# MAIN.net
KiCad netlist of a schematic drawn in Altium Designer
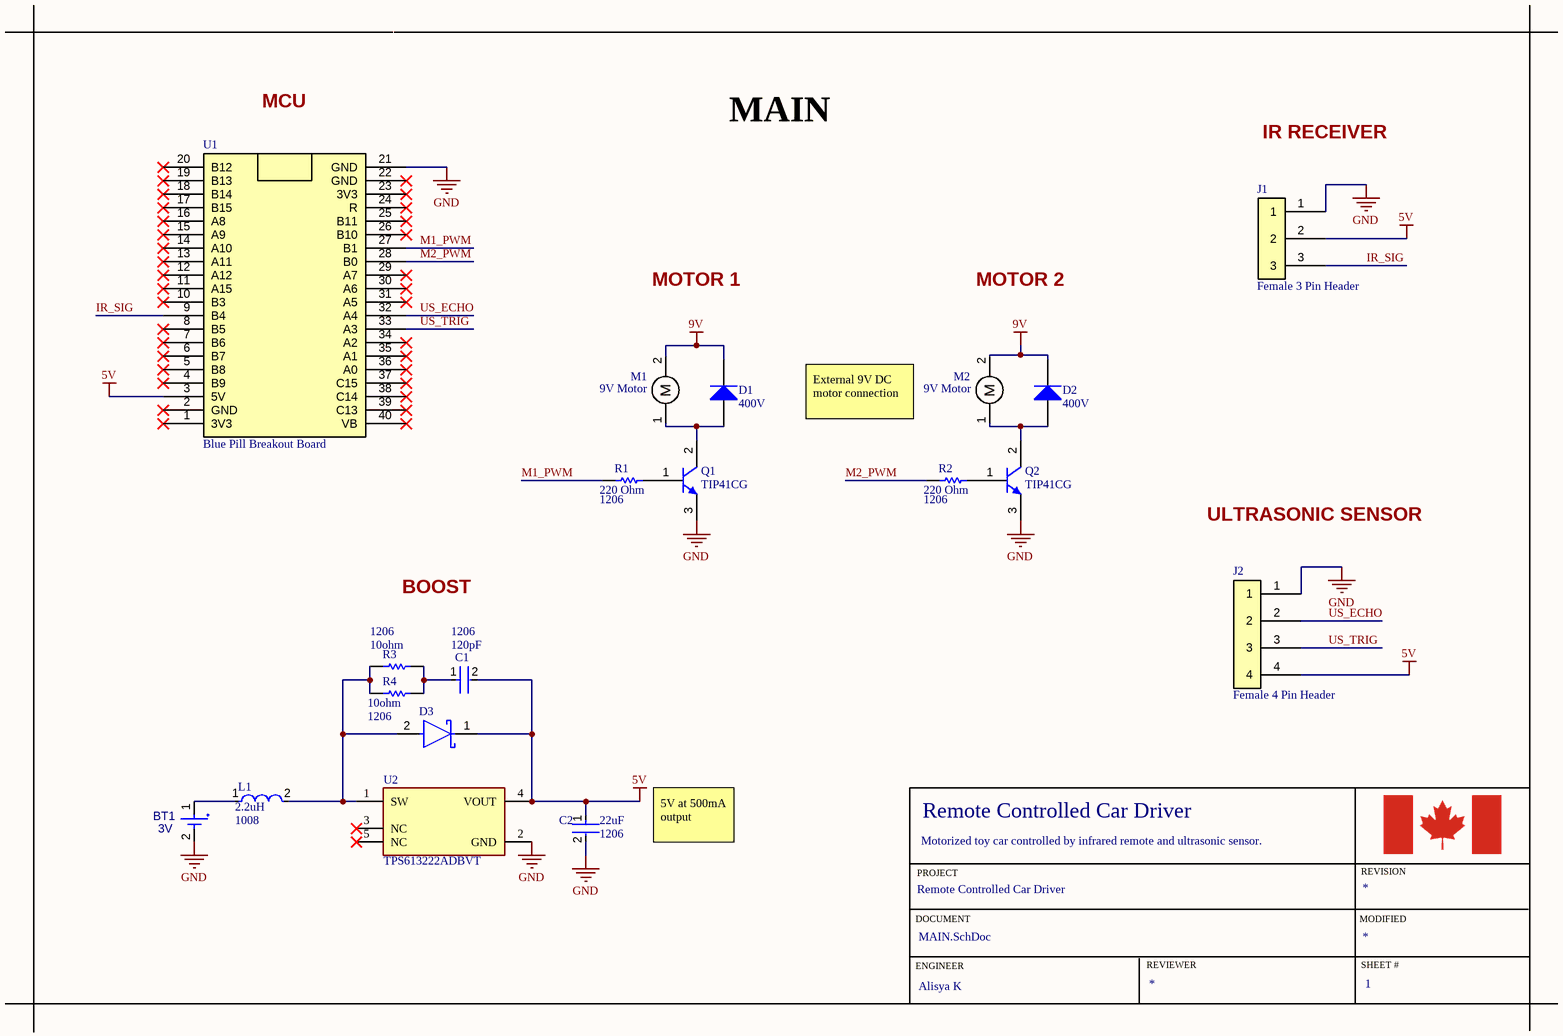
[diagram p0: MAIN.SchDoc]

(export (version "E")
  (design (tool "Eeschema 10.0.6"))
  (components
    (comp (ref "BT1")
      (value "3V")
      (footprint "New footprint 1")
      (libsource (lib "pcb stuff") (part "CMP-00622-2"))
    )
    (comp (ref "C1")
      (value "GRM31A7U3A121JW31D")
      (footprint "FP-GRM31A-0_2-e0_3_0_95-IPC_B")
      (description "Chip Multilayer Ceramic Capacitors for General Purpose, 1206, 120pF, U2J, -750ppm/°C, 5%, 1kV")
      (fields
        (field (name "CASE/PACKAGE") "1206")
        (field (name "TOLERANCE") "5%")
        (field (name "CAPACITANCE") "120pF")
      )
      (libsource (lib "Altium Content Vault") (part "b4654b650e69147ec39a6b967a45e02"))
    )
    (comp (ref "C2")
      (value "C3216X5R1V226M160AC")
      (footprint "FP-C3216-160-0_2-IPC_B")
      (description "Multilayer Ceramic Capacitors 22uF ±20% 35V X5R SMD 1206")
      (fields
        (field (name "CASE/PACKAGE") "1206")
        (field (name "TOLERANCE") "20%")
        (field (name "VOLTAGE") "35V")
        (field (name "CAPACITANCE") "22uF")
      )
      (libsource (lib "Altium Content Vault") (part "11868f565c42a9108669ba33697ecf6"))
    )
    (comp (ref "D1")
      (value "S1G-13-F")
      (footprint "DIOD-SMA-2_V")
      (description "Glass Passivated Rectifier, 1 A, 400 V, -65 to 150 degC, 2-Pin SMD, RoHS, Tape and Reel")
      (fields (field (name "REVERSE VOLTAGE-MAX [VRRM]") "400V") (field (name "MANUFACTURER") "Diodes Inc"))
      (libsource (lib "Altium Content Vault") (part "D-AK-2"))
    )
    (comp (ref "D2")
      (value "S1G-13-F")
      (footprint "DIOD-SMA-2_V")
      (description "Glass Passivated Rectifier, 1 A, 400 V, -65 to 150 degC, 2-Pin SMD, RoHS, Tape and Reel")
      (fields (field (name "REVERSE VOLTAGE-MAX [VRRM]") "400V") (field (name "MANUFACTURER") "Diodes Inc"))
      (libsource (lib "Altium Content Vault") (part "D-AK-2"))
    )
    (comp (ref "D3")
      (value "MSS1P4-M3/89A")
      (footprint "FP-96591-MFG")
      (description "DIODE SCHOTTKY 40V 1A MICROSMP")
      (fields
        (field (name "OCTOPART") "https://octopart.com/mss1p4-m3%2F89a-vishay-42505723")
        (field (name "MANUFACTURER") "Vishay")
      )
      (libsource (lib "Altium Content Vault") (part "c1678fac7984e62e0809fbf79c06691"))
    )
    (comp (ref "J1")
      (value "Female 3 Pin Header")
      (footprint "Female 4 Pin Header-Footprint-1")
      (libsource (lib "pcb stuff") (part "Female 3 Pin Header-Symbol-1"))
    )
    (comp (ref "J2")
      (value "Female 4 Pin Header")
      (footprint "Female 4 Pin Header-Footprint-1")
      (libsource (lib "pcb stuff") (part "Female 4 Pin Header-Symbol-1"))
    )
    (comp (ref "L1")
      (value "DFE252012F-2R2M=P2")
      (footprint "FP-DFE252012C-IPC_B")
      (description "Shielded Wirewound Inductor 2.2uH 20% 2300mA 0.082Ω 1008 (2520)")
      (fields
        (field (name "CASE/PACKAGE") "1008")
        (field (name "TOLERANCE") "20%")
        (field (name "INDUCTANCE") "2.2uH")
      )
      (libsource (lib "Altium Content Vault") (part "725321dda6339637d4d059423bc1c3c"))
    )
    (comp (ref "M1")
      (value "9V Motor")
      (footprint "9V Motor-Footprint-1")
      (libsource (lib "pcb stuff") (part "9V Motor-Symbol-1"))
    )
    (comp (ref "M2")
      (value "9V Motor")
      (footprint "9V Motor-Footprint-1")
      (libsource (lib "pcb stuff") (part "9V Motor-Symbol-1"))
    )
    (comp (ref "Q1")
      (value "TIP41CG")
      (footprint "ONSC-TO-220-3-221A-09")
      (description "Complementary Silicon Plastic Power Transistor, 3-Pin TO-220, Pb-Free, Tube")
      (fields (field (name "MANUFACTURER") "On Semiconductor"))
      (libsource (lib "Altium Content Vault") (part "ONSC-NPN-B1C2E3-3_C"))
    )
    (comp (ref "Q2")
      (value "TIP41CG")
      (footprint "ONSC-TO-220-3-221A-09")
      (description "Complementary Silicon Plastic Power Transistor, 3-Pin TO-220, Pb-Free, Tube")
      (fields (field (name "MANUFACTURER") "On Semiconductor"))
      (libsource (lib "Altium Content Vault") (part "ONSC-NPN-B1C2E3-3_C"))
    )
    (comp (ref "R1")
      (value "220 Ohm")
      (footprint "RESC3216X60X45ML10T20")
      (fields
        (field (name "MANUFACTURER") "Vishay Dale")
        (field (name "PART NUMBER") "CRCW1206220RFKEA")
        (field (name "PACKAGE") "1206")
      )
      (libsource (lib "Altium Content Vault") (part "RES"))
    )
    (comp (ref "R2")
      (value "220 Ohm")
      (footprint "RESC3216X60X45ML10T20")
      (fields
        (field (name "MANUFACTURER") "Vishay Dale")
        (field (name "PART NUMBER") "CRCW1206220RFKEA")
        (field (name "PACKAGE") "1206")
      )
      (libsource (lib "Altium Content Vault") (part "RES"))
    )
    (comp (ref "R3")
      (value "10ohm")
      (footprint "RESC3216X60X45NL10T20")
      (fields
        (field (name "PART NUMBER") "CRCW120610R0FKTA")
        (field (name "MANUFACTURER") "Vishay Dale")
        (field (name "PACKAGE") "1206")
      )
      (libsource (lib "Altium Content Vault") (part "RES"))
    )
    (comp (ref "R4")
      (value "10ohm")
      (footprint "RESC3216X60X45NL10T20")
      (fields
        (field (name "PART NUMBER") "CRCW120610R0FKTA")
        (field (name "MANUFACTURER") "Vishay Dale")
        (field (name "PACKAGE") "1206")
      )
      (libsource (lib "Altium Content Vault") (part "RES"))
    )
    (comp (ref "U1")
      (value "Blue Pill Breakout Board")
      (footprint "Blue Pill Breakout Board-Footprint-1")
      (description "STM32F103C6T6A")
      (libsource (lib "pcb stuff") (part "Blue Pill Breakout Board-Symbol-1"))
    )
    (comp (ref "U2")
      (value "TPS613222ADBVT")
      (footprint "FP-DBV0005A-MFG")
      (description "IC REG BOOST 5V 2.5A SOT23-5")
      (libsource (lib "Altium Content Vault") (part "046d2554ad9af14250d30b20e3f80a1"))
    )
  )
  (nets
    (net (code "1") (name "/IR_SIG") (class "Default")
      (node (ref "J1") (pin "3") (pinfunction "3_3") (pintype "passive"))
      (node (ref "U1") (pin "9") (pinfunction "B4_9") (pintype "passive"))
    )
    (net (code "2") (name "/M1_PWM") (class "Default")
      (node (ref "R1") (pin "1") (pinfunction "1_1") (pintype "passive"))
      (node (ref "U1") (pin "27") (pinfunction "B1_27") (pintype "passive"))
    )
    (net (code "3") (name "/M2_PWM") (class "Default")
      (node (ref "R2") (pin "1") (pinfunction "1_1") (pintype "passive"))
      (node (ref "U1") (pin "28") (pinfunction "B0_28") (pintype "passive"))
    )
    (net (code "4") (name "/US_ECHO") (class "Default")
      (node (ref "J2") (pin "2") (pinfunction "2_2") (pintype "passive"))
      (node (ref "U1") (pin "32") (pinfunction "A4_32") (pintype "passive"))
    )
    (net (code "5") (name "/US_TRIG") (class "Default")
      (node (ref "J2") (pin "3") (pinfunction "3_3") (pintype "passive"))
      (node (ref "U1") (pin "33") (pinfunction "A3_33") (pintype "passive"))
    )
    (net (code "6") (name "5V") (class "Default")
      (node (ref "C1") (pin "2") (pinfunction "2_2") (pintype "passive"))
      (node (ref "C2") (pin "1") (pinfunction "1_1") (pintype "passive"))
      (node (ref "D3") (pin "1") (pinfunction "C_1") (pintype "passive"))
      (node (ref "J1") (pin "2") (pinfunction "2_2") (pintype "passive"))
      (node (ref "J2") (pin "4") (pinfunction "4_4") (pintype "passive"))
      (node (ref "U1") (pin "3") (pinfunction "5V_3") (pintype "passive"))
      (node (ref "U2") (pin "4") (pinfunction "VOUT_4") (pintype "power_in"))
    )
    (net (code "7") (name "9V") (class "Default")
      (node (ref "D1") (pin "2") (pinfunction "K_2") (pintype "passive"))
      (node (ref "D2") (pin "2") (pinfunction "K_2") (pintype "passive"))
      (node (ref "M1") (pin "2") (pinfunction "19_2") (pintype "passive"))
      (node (ref "M2") (pin "2") (pinfunction "19_2") (pintype "passive"))
    )
    (net (code "8") (name "GND") (class "Default")
      (node (ref "BT1") (pin "2") (pinfunction "-_2") (pintype "passive"))
      (node (ref "C2") (pin "2") (pinfunction "2_2") (pintype "passive"))
      (node (ref "J1") (pin "1") (pinfunction "1_1") (pintype "passive"))
      (node (ref "J2") (pin "1") (pinfunction "1_1") (pintype "passive"))
      (node (ref "Q1") (pin "3") (pinfunction "E_3") (pintype "passive"))
      (node (ref "Q2") (pin "3") (pinfunction "E_3") (pintype "passive"))
      (node (ref "U1") (pin "21") (pinfunction "GND_21") (pintype "passive"))
      (node (ref "U2") (pin "2") (pinfunction "GND_2") (pintype "power_in"))
    )
    (net (code "9") (name "Net-(BT1-+)") (class "Default")
      (node (ref "BT1") (pin "1") (pinfunction "+_1") (pintype "passive"))
      (node (ref "L1") (pin "1") (pinfunction "1_1") (pintype "passive"))
    )
    (net (code "10") (name "Net-(C1-Pad1)") (class "Default")
      (node (ref "C1") (pin "1") (pinfunction "1_1") (pintype "passive"))
      (node (ref "R3") (pin "2") (pinfunction "2_2") (pintype "passive"))
      (node (ref "R4") (pin "2") (pinfunction "2_2") (pintype "passive"))
    )
    (net (code "11") (name "Net-(D1-A)") (class "Default")
      (node (ref "D1") (pin "1") (pinfunction "A_1") (pintype "passive"))
      (node (ref "M1") (pin "1") (pinfunction "18_1") (pintype "passive"))
      (node (ref "Q1") (pin "2") (pinfunction "C_2") (pintype "passive"))
    )
    (net (code "12") (name "Net-(D2-A)") (class "Default")
      (node (ref "D2") (pin "1") (pinfunction "A_1") (pintype "passive"))
      (node (ref "M2") (pin "1") (pinfunction "18_1") (pintype "passive"))
      (node (ref "Q2") (pin "2") (pinfunction "C_2") (pintype "passive"))
    )
    (net (code "13") (name "Net-(D3-A)") (class "Default")
      (node (ref "D3") (pin "2") (pinfunction "A_2") (pintype "passive"))
      (node (ref "L1") (pin "2") (pinfunction "2_2") (pintype "passive"))
      (node (ref "R3") (pin "1") (pinfunction "1_1") (pintype "passive"))
      (node (ref "R4") (pin "1") (pinfunction "1_1") (pintype "passive"))
      (node (ref "U2") (pin "1") (pinfunction "SW_1") (pintype "passive"))
    )
    (net (code "14") (name "Net-(Q1-B)") (class "Default")
      (node (ref "Q1") (pin "1") (pinfunction "B_1") (pintype "passive"))
      (node (ref "R1") (pin "2") (pinfunction "2_2") (pintype "passive"))
    )
    (net (code "15") (name "Net-(Q2-B)") (class "Default")
      (node (ref "Q2") (pin "1") (pinfunction "B_1") (pintype "passive"))
      (node (ref "R2") (pin "2") (pinfunction "2_2") (pintype "passive"))
    )
    (net (code "16") (name "unconnected-(U1-3V3-Pad1)") (class "Default")
      (node (ref "U1") (pin "1") (pinfunction "3V3_1") (pintype "passive+no_connect"))
    )
    (net (code "17") (name "unconnected-(U1-3V3-Pad23)") (class "Default")
      (node (ref "U1") (pin "23") (pinfunction "3V3_23") (pintype "passive+no_connect"))
    )
    (net (code "18") (name "unconnected-(U1-A0-Pad36)") (class "Default")
      (node (ref "U1") (pin "36") (pinfunction "A0_36") (pintype "passive+no_connect"))
    )
    (net (code "19") (name "unconnected-(U1-A1-Pad35)") (class "Default")
      (node (ref "U1") (pin "35") (pinfunction "A1_35") (pintype "passive+no_connect"))
    )
    (net (code "20") (name "unconnected-(U1-A2-Pad34)") (class "Default")
      (node (ref "U1") (pin "34") (pinfunction "A2_34") (pintype "passive+no_connect"))
    )
    (net (code "21") (name "unconnected-(U1-A5-Pad31)") (class "Default")
      (node (ref "U1") (pin "31") (pinfunction "A5_31") (pintype "passive+no_connect"))
    )
    (net (code "22") (name "unconnected-(U1-A6-Pad30)") (class "Default")
      (node (ref "U1") (pin "30") (pinfunction "A6_30") (pintype "passive+no_connect"))
    )
    (net (code "23") (name "unconnected-(U1-A7-Pad29)") (class "Default")
      (node (ref "U1") (pin "29") (pinfunction "A7_29") (pintype "passive+no_connect"))
    )
    (net (code "24") (name "unconnected-(U1-A8-Pad16)") (class "Default")
      (node (ref "U1") (pin "16") (pinfunction "A8_16") (pintype "passive+no_connect"))
    )
    (net (code "25") (name "unconnected-(U1-A9-Pad15)") (class "Default")
      (node (ref "U1") (pin "15") (pinfunction "A9_15") (pintype "passive+no_connect"))
    )
    (net (code "26") (name "unconnected-(U1-A10-Pad14)") (class "Default")
      (node (ref "U1") (pin "14") (pinfunction "A10_14") (pintype "passive+no_connect"))
    )
    (net (code "27") (name "unconnected-(U1-A11-Pad13)") (class "Default")
      (node (ref "U1") (pin "13") (pinfunction "A11_13") (pintype "passive+no_connect"))
    )
    (net (code "28") (name "unconnected-(U1-A12-Pad12)") (class "Default")
      (node (ref "U1") (pin "12") (pinfunction "A12_12") (pintype "passive+no_connect"))
    )
    (net (code "29") (name "unconnected-(U1-A15-Pad11)") (class "Default")
      (node (ref "U1") (pin "11") (pinfunction "A15_11") (pintype "passive+no_connect"))
    )
    (net (code "30") (name "unconnected-(U1-B3-Pad10)") (class "Default")
      (node (ref "U1") (pin "10") (pinfunction "B3_10") (pintype "passive+no_connect"))
    )
    (net (code "31") (name "unconnected-(U1-B5-Pad8)") (class "Default")
      (node (ref "U1") (pin "8") (pinfunction "B5_8") (pintype "passive+no_connect"))
    )
    (net (code "32") (name "unconnected-(U1-B6-Pad7)") (class "Default")
      (node (ref "U1") (pin "7") (pinfunction "B6_7") (pintype "passive+no_connect"))
    )
    (net (code "33") (name "unconnected-(U1-B7-Pad6)") (class "Default")
      (node (ref "U1") (pin "6") (pinfunction "B7_6") (pintype "passive+no_connect"))
    )
    (net (code "34") (name "unconnected-(U1-B8-Pad5)") (class "Default")
      (node (ref "U1") (pin "5") (pinfunction "B8_5") (pintype "passive+no_connect"))
    )
    (net (code "35") (name "unconnected-(U1-B9-Pad4)") (class "Default")
      (node (ref "U1") (pin "4") (pinfunction "B9_4") (pintype "passive+no_connect"))
    )
    (net (code "36") (name "unconnected-(U1-B10-Pad26)") (class "Default")
      (node (ref "U1") (pin "26") (pinfunction "B10_26") (pintype "passive+no_connect"))
    )
    (net (code "37") (name "unconnected-(U1-B11-Pad25)") (class "Default")
      (node (ref "U1") (pin "25") (pinfunction "B11_25") (pintype "passive+no_connect"))
    )
    (net (code "38") (name "unconnected-(U1-B12-Pad20)") (class "Default")
      (node (ref "U1") (pin "20") (pinfunction "B12_20") (pintype "passive+no_connect"))
    )
    (net (code "39") (name "unconnected-(U1-B13-Pad19)") (class "Default")
      (node (ref "U1") (pin "19") (pinfunction "B13_19") (pintype "passive+no_connect"))
    )
    (net (code "40") (name "unconnected-(U1-B14-Pad18)") (class "Default")
      (node (ref "U1") (pin "18") (pinfunction "B14_18") (pintype "passive+no_connect"))
    )
    (net (code "41") (name "unconnected-(U1-B15-Pad17)") (class "Default")
      (node (ref "U1") (pin "17") (pinfunction "B15_17") (pintype "passive+no_connect"))
    )
    (net (code "42") (name "unconnected-(U1-C13-Pad39)") (class "Default")
      (node (ref "U1") (pin "39") (pinfunction "C13_39") (pintype "passive+no_connect"))
    )
    (net (code "43") (name "unconnected-(U1-C14-Pad38)") (class "Default")
      (node (ref "U1") (pin "38") (pinfunction "C14_38") (pintype "passive+no_connect"))
    )
    (net (code "44") (name "unconnected-(U1-C15-Pad37)") (class "Default")
      (node (ref "U1") (pin "37") (pinfunction "C15_37") (pintype "passive+no_connect"))
    )
    (net (code "45") (name "unconnected-(U1-GND-Pad2)") (class "Default")
      (node (ref "U1") (pin "2") (pinfunction "GND_2") (pintype "passive+no_connect"))
    )
    (net (code "46") (name "unconnected-(U1-GND-Pad22)") (class "Default")
      (node (ref "U1") (pin "22") (pinfunction "GND_22") (pintype "passive+no_connect"))
    )
    (net (code "47") (name "unconnected-(U1-R-Pad24)") (class "Default")
      (node (ref "U1") (pin "24") (pinfunction "R_24") (pintype "passive+no_connect"))
    )
    (net (code "48") (name "unconnected-(U1-VB-Pad40)") (class "Default")
      (node (ref "U1") (pin "40") (pinfunction "VB_40") (pintype "passive+no_connect"))
    )
    (net (code "49") (name "unconnected-(U2-NC-Pad3)") (class "Default")
      (node (ref "U2") (pin "3") (pinfunction "NC_3") (pintype "passive+no_connect"))
    )
    (net (code "50") (name "unconnected-(U2-NC-Pad5)") (class "Default")
      (node (ref "U2") (pin "5") (pinfunction "NC_5") (pintype "passive+no_connect"))
    )
  )
)
